# Hall_measurement.net
KiCad netlist of a schematic drawn in Altium Designer
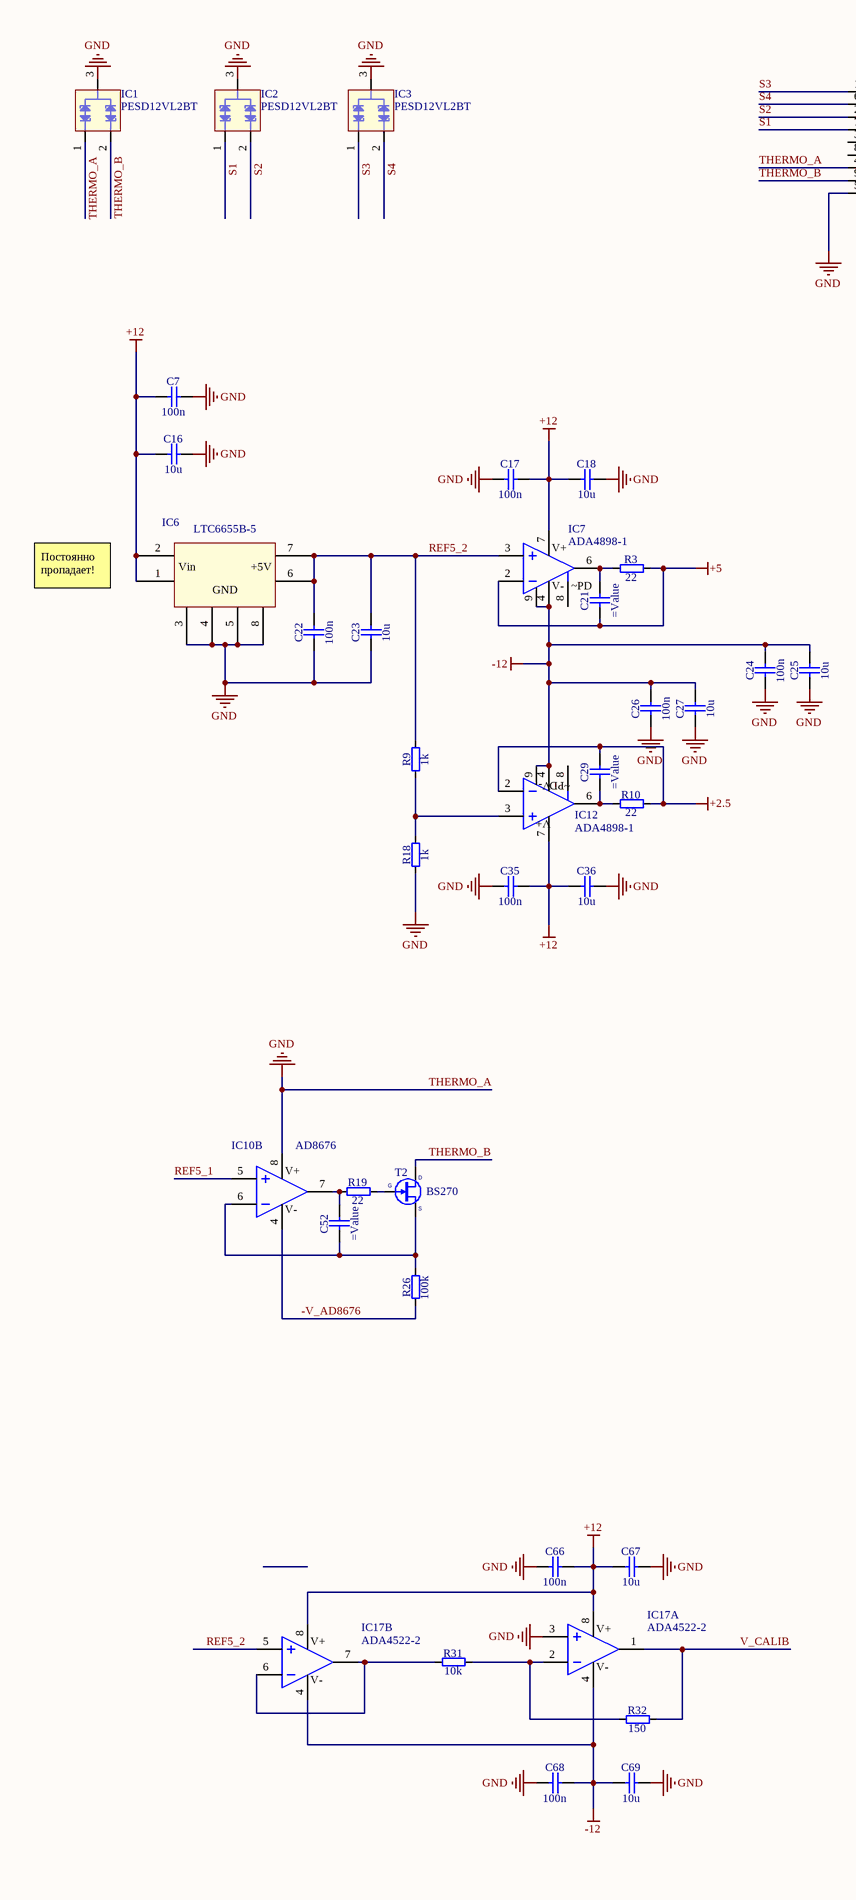
[diagram p0: Hall_measurement.SchDoc, left]
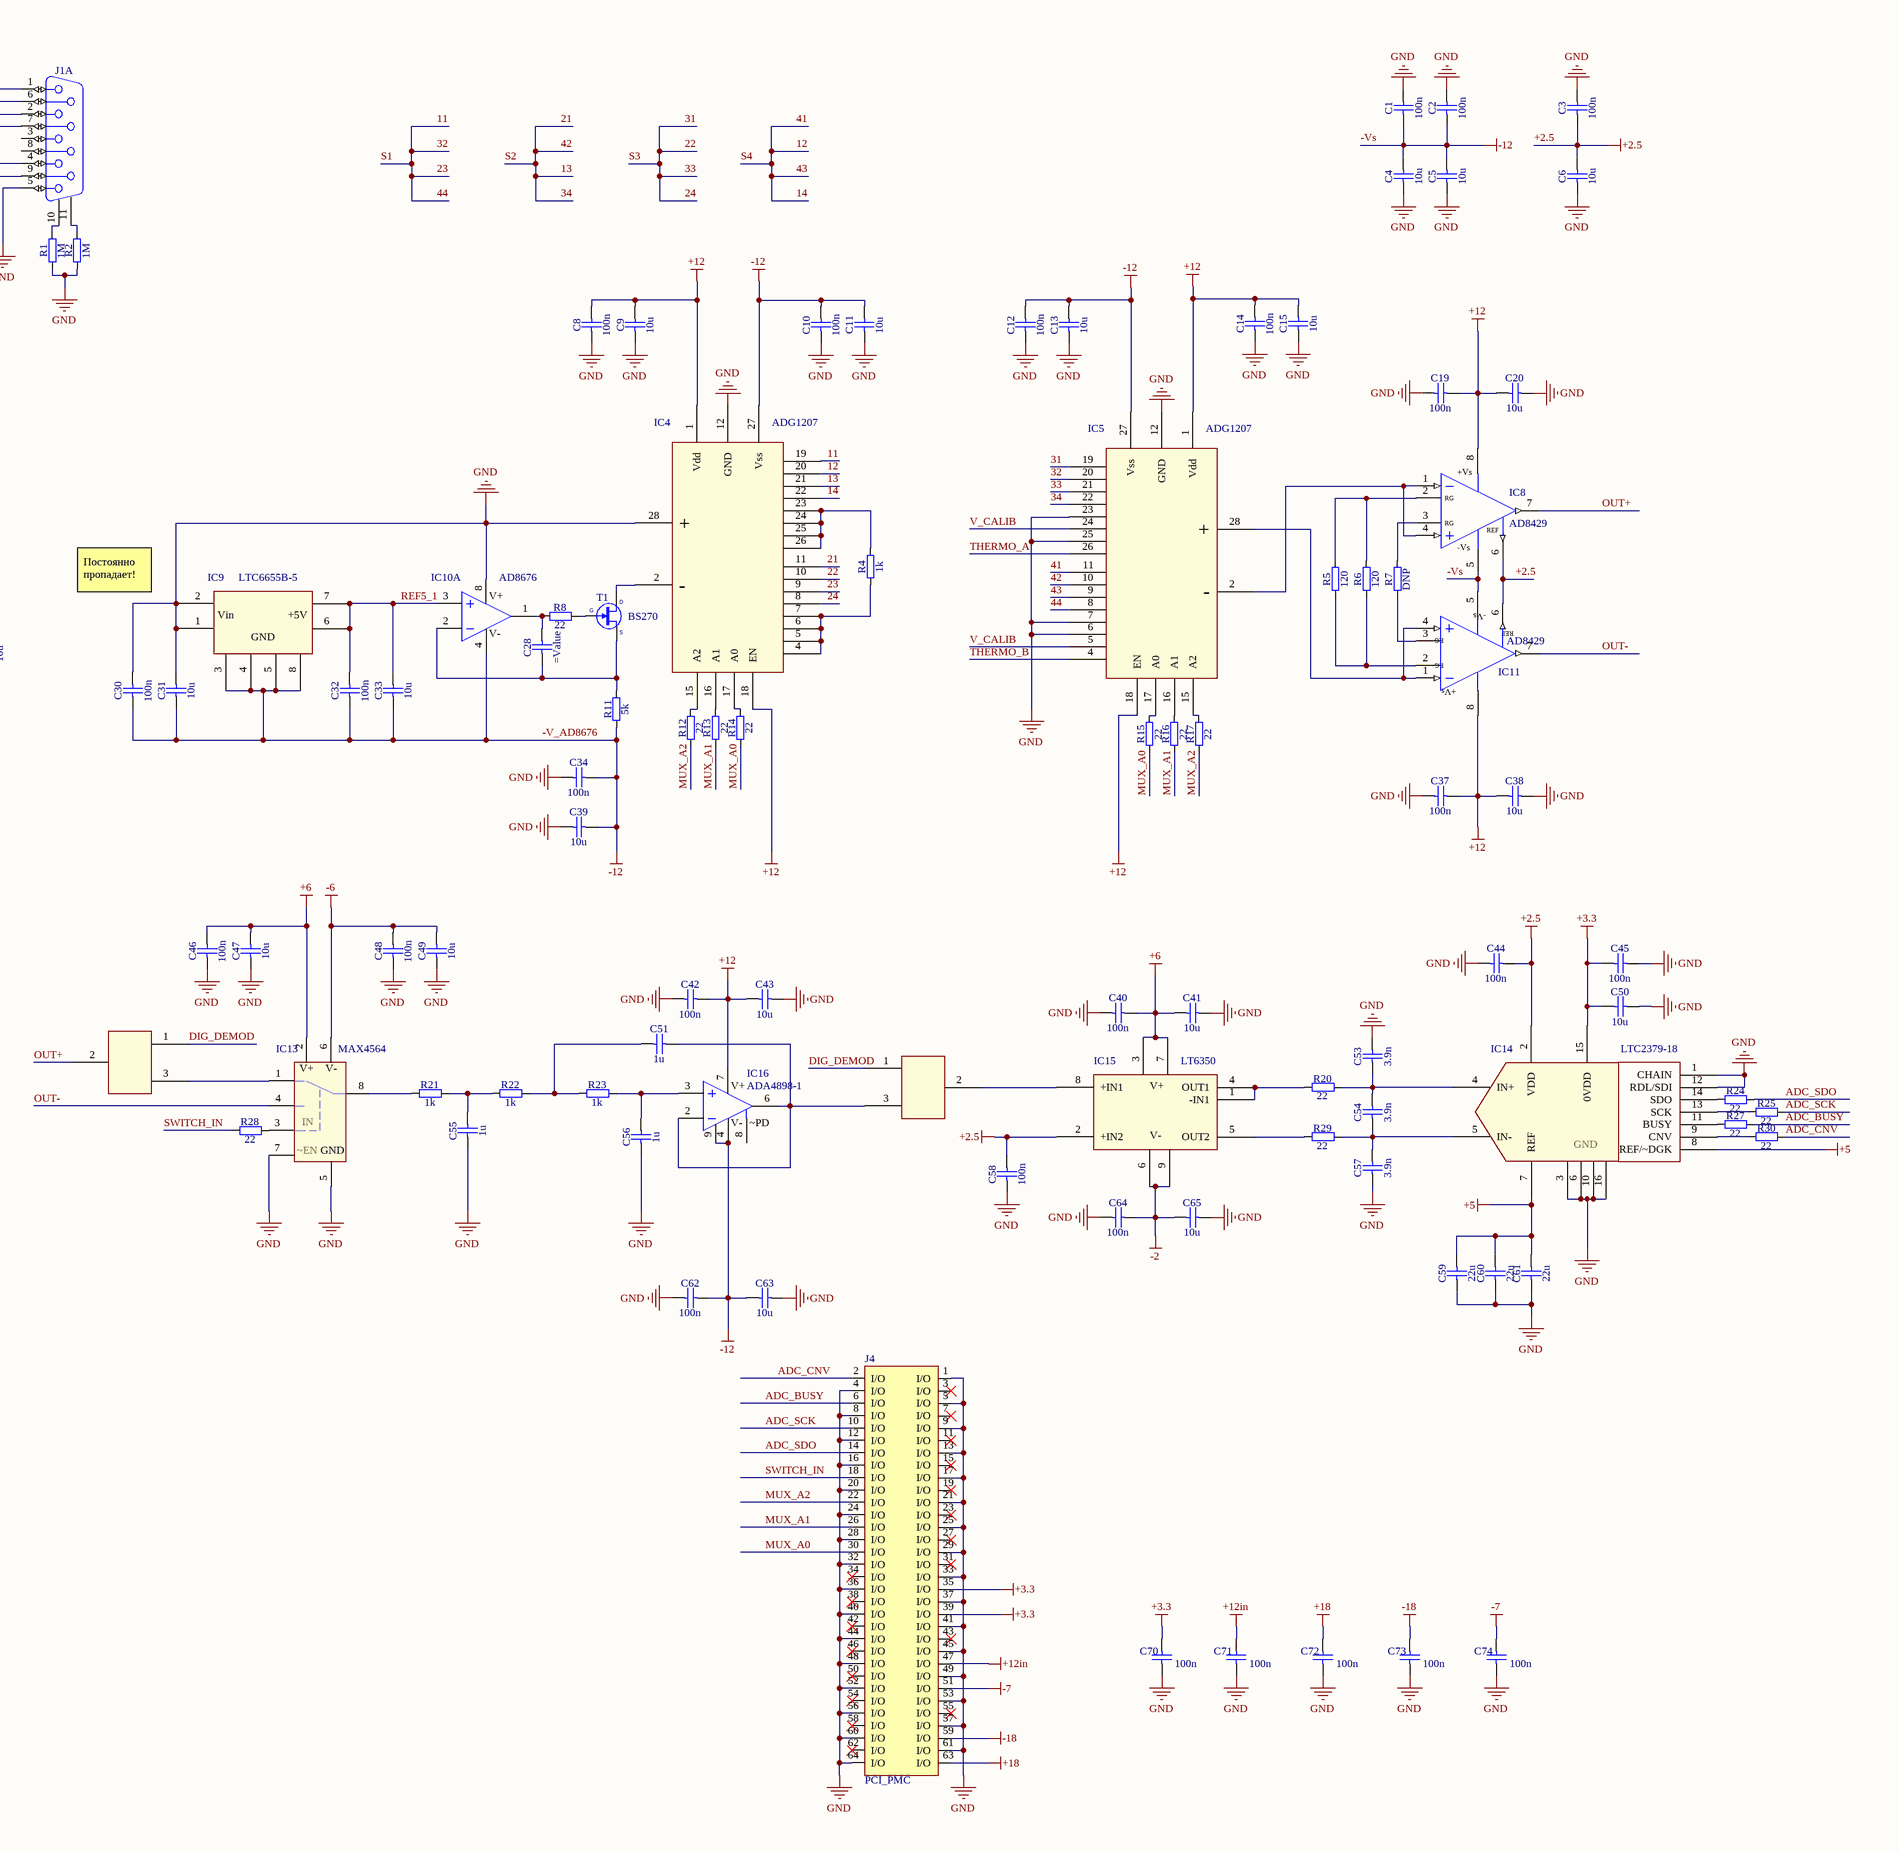
[diagram p1: Hall_measurement.SchDoc, right]

(export (version "E")
  (design (tool "Eeschema 10.0.6"))
  (components
    (comp (ref "C1") (value "100n") (footprint "0603") (libsource (lib "Lib2408_Hall") (part "Capacitor")))
    (comp (ref "C2") (value "100n") (footprint "0603") (libsource (lib "Lib2408_Hall") (part "Capacitor")))
    (comp (ref "C3") (value "100n") (footprint "0603") (libsource (lib "Lib2408_Hall") (part "Capacitor")))
    (comp (ref "C4") (value "10u") (footprint "0603") (libsource (lib "Lib2408_Hall") (part "Capacitor")))
    (comp (ref "C5") (value "10u") (footprint "0603") (libsource (lib "Lib2408_Hall") (part "Capacitor")))
    (comp (ref "C6") (value "10u") (footprint "0603") (libsource (lib "Lib2408_Hall") (part "Capacitor")))
    (comp (ref "C7") (value "100n") (footprint "0603") (libsource (lib "Lib2408_Hall") (part "Capacitor")))
    (comp (ref "C8") (value "100n") (footprint "0603") (libsource (lib "Lib2408_Hall") (part "Capacitor")))
    (comp (ref "C9") (value "10u") (footprint "0603") (libsource (lib "Lib2408_Hall") (part "Capacitor")))
    (comp (ref "C10") (value "100n") (footprint "0603") (libsource (lib "Lib2408_Hall") (part "Capacitor")))
    (comp (ref "C11") (value "10u") (footprint "0603") (libsource (lib "Lib2408_Hall") (part "Capacitor")))
    (comp (ref "C12") (value "100n") (footprint "0603") (libsource (lib "Lib2408_Hall") (part "Capacitor")))
    (comp (ref "C13") (value "10u") (footprint "0603") (libsource (lib "Lib2408_Hall") (part "Capacitor")))
    (comp (ref "C14") (value "100n") (footprint "0603") (libsource (lib "Lib2408_Hall") (part "Capacitor")))
    (comp (ref "C15") (value "10u") (footprint "0603") (libsource (lib "Lib2408_Hall") (part "Capacitor")))
    (comp (ref "C16") (value "10u") (footprint "0603") (libsource (lib "Lib2408_Hall") (part "Capacitor")))
    (comp (ref "C17") (value "100n") (footprint "0603") (libsource (lib "Lib2408_Hall") (part "Capacitor")))
    (comp (ref "C18") (value "10u") (footprint "0603") (libsource (lib "Lib2408_Hall") (part "Capacitor")))
    (comp (ref "C19") (value "100n") (footprint "0603") (libsource (lib "Lib2408_Hall") (part "Capacitor")))
    (comp (ref "C20") (value "10u") (footprint "0603") (libsource (lib "Lib2408_Hall") (part "Capacitor")))
    (comp (ref "C21") (value "~") (footprint "0603") (libsource (lib "Lib2408_Hall") (part "Capacitor")))
    (comp (ref "C22") (value "100n") (footprint "0603") (libsource (lib "Lib2408_Hall") (part "Capacitor")))
    (comp (ref "C23") (value "10u") (footprint "0603") (libsource (lib "Lib2408_Hall") (part "Capacitor")))
    (comp (ref "C24") (value "100n") (footprint "0603") (libsource (lib "Lib2408_Hall") (part "Capacitor")))
    (comp (ref "C25") (value "10u") (footprint "0603") (libsource (lib "Lib2408_Hall") (part "Capacitor")))
    (comp (ref "C26") (value "100n") (footprint "0603") (libsource (lib "Lib2408_Hall") (part "Capacitor")))
    (comp (ref "C27") (value "10u") (footprint "0603") (libsource (lib "Lib2408_Hall") (part "Capacitor")))
    (comp (ref "C28") (value "~") (footprint "0603") (libsource (lib "Lib2408_Hall") (part "Capacitor")))
    (comp (ref "C29") (value "~") (footprint "0603") (libsource (lib "Lib2408_Hall") (part "Capacitor")))
    (comp (ref "C30") (value "100n") (footprint "0603") (libsource (lib "Lib2408_Hall") (part "Capacitor")))
    (comp (ref "C31") (value "10u") (footprint "0603") (libsource (lib "Lib2408_Hall") (part "Capacitor")))
    (comp (ref "C32") (value "100n") (footprint "0603") (libsource (lib "Lib2408_Hall") (part "Capacitor")))
    (comp (ref "C33") (value "10u") (footprint "0603") (libsource (lib "Lib2408_Hall") (part "Capacitor")))
    (comp (ref "C34") (value "100n") (footprint "0603") (libsource (lib "Lib2408_Hall") (part "Capacitor")))
    (comp (ref "C35") (value "100n") (footprint "0603") (libsource (lib "Lib2408_Hall") (part "Capacitor")))
    (comp (ref "C36") (value "10u") (footprint "0603") (libsource (lib "Lib2408_Hall") (part "Capacitor")))
    (comp (ref "C37") (value "100n") (footprint "0603") (libsource (lib "Lib2408_Hall") (part "Capacitor")))
    (comp (ref "C38") (value "10u") (footprint "0603") (libsource (lib "Lib2408_Hall") (part "Capacitor")))
    (comp (ref "C39") (value "10u") (footprint "0603") (libsource (lib "Lib2408_Hall") (part "Capacitor")))
    (comp (ref "C40") (value "100n") (footprint "0603") (libsource (lib "Lib2408_Hall") (part "Capacitor")))
    (comp (ref "C41") (value "10u") (footprint "0603") (libsource (lib "Lib2408_Hall") (part "Capacitor")))
    (comp (ref "C42") (value "100n") (footprint "0603") (libsource (lib "Lib2408_Hall") (part "Capacitor")))
    (comp (ref "C43") (value "10u") (footprint "0603") (libsource (lib "Lib2408_Hall") (part "Capacitor")))
    (comp (ref "C44") (value "100n") (footprint "0603") (libsource (lib "Lib2408_Hall") (part "Capacitor")))
    (comp (ref "C45") (value "100n") (footprint "0603") (libsource (lib "Lib2408_Hall") (part "Capacitor")))
    (comp (ref "C46") (value "100n") (footprint "0603") (libsource (lib "Lib2408_Hall") (part "Capacitor")))
    (comp (ref "C47") (value "10u") (footprint "0603") (libsource (lib "Lib2408_Hall") (part "Capacitor")))
    (comp (ref "C48") (value "100n") (footprint "0603") (libsource (lib "Lib2408_Hall") (part "Capacitor")))
    (comp (ref "C49") (value "10u") (footprint "0603") (libsource (lib "Lib2408_Hall") (part "Capacitor")))
    (comp (ref "C50") (value "10u") (footprint "0603") (libsource (lib "Lib2408_Hall") (part "Capacitor")))
    (comp (ref "C51")
      (value "1u")
      (footprint "CAPR500-450X730X950")
      (libsource (lib "Lib2408_Hall") (part "Capacitor 4.5mm x 7.3mm"))
    )
    (comp (ref "C52") (value "~") (footprint "0603") (libsource (lib "Lib2408_Hall") (part "Capacitor")))
    (comp (ref "C53") (value "3.9n") (footprint "0805") (libsource (lib "Lib2408_Hall") (part "Capacitor")))
    (comp (ref "C54") (value "3.9n") (footprint "0805") (libsource (lib "Lib2408_Hall") (part "Capacitor")))
    (comp (ref "C55")
      (value "1u")
      (footprint "CAPR500-450X730X950")
      (libsource (lib "Lib2408_Hall") (part "Capacitor 4.5mm x 7.3mm"))
    )
    (comp (ref "C56")
      (value "1u")
      (footprint "CAPR500-450X730X950")
      (libsource (lib "Lib2408_Hall") (part "Capacitor 4.5mm x 7.3mm"))
    )
    (comp (ref "C57") (value "3.9n") (footprint "0805") (libsource (lib "Lib2408_Hall") (part "Capacitor")))
    (comp (ref "C58") (value "100n") (footprint "0603") (libsource (lib "Lib2408_Hall") (part "Capacitor")))
    (comp (ref "C59") (value "22u") (footprint "0603") (libsource (lib "Lib2408_Hall") (part "Capacitor")))
    (comp (ref "C60") (value "22u") (footprint "0603") (libsource (lib "Lib2408_Hall") (part "Capacitor")))
    (comp (ref "C61") (value "22u") (footprint "0603") (libsource (lib "Lib2408_Hall") (part "Capacitor")))
    (comp (ref "C62") (value "100n") (footprint "0603") (libsource (lib "Lib2408_Hall") (part "Capacitor")))
    (comp (ref "C63") (value "10u") (footprint "0603") (libsource (lib "Lib2408_Hall") (part "Capacitor")))
    (comp (ref "C64") (value "100n") (footprint "0603") (libsource (lib "Lib2408_Hall") (part "Capacitor")))
    (comp (ref "C65") (value "10u") (footprint "0603") (libsource (lib "Lib2408_Hall") (part "Capacitor")))
    (comp (ref "C66") (value "100n") (footprint "0603") (libsource (lib "Lib2408_Hall") (part "Capacitor")))
    (comp (ref "C67") (value "10u") (footprint "0603") (libsource (lib "Lib2408_Hall") (part "Capacitor")))
    (comp (ref "C68") (value "100n") (footprint "0603") (libsource (lib "Lib2408_Hall") (part "Capacitor")))
    (comp (ref "C69") (value "10u") (footprint "0603") (libsource (lib "Lib2408_Hall") (part "Capacitor")))
    (comp (ref "C70") (value "100n") (footprint "0603") (libsource (lib "Lib2408_Hall") (part "Capacitor")))
    (comp (ref "C71") (value "100n") (footprint "0603") (libsource (lib "Lib2408_Hall") (part "Capacitor")))
    (comp (ref "C72") (value "100n") (footprint "0603") (libsource (lib "Lib2408_Hall") (part "Capacitor")))
    (comp (ref "C73") (value "100n") (footprint "0603") (libsource (lib "Lib2408_Hall") (part "Capacitor")))
    (comp (ref "C74") (value "100n") (footprint "0603") (libsource (lib "Lib2408_Hall") (part "Capacitor")))
    (comp (ref "IC1")
      (value "PESD12VL2BT")
      (footprint "SOT95P280X115-3N")
      (libsource (lib "Lib2408_Hall") (part "PESD12VL2BT"))
    )
    (comp (ref "IC2")
      (value "PESD12VL2BT")
      (footprint "SOT95P280X115-3N")
      (libsource (lib "Lib2408_Hall") (part "PESD12VL2BT"))
    )
    (comp (ref "IC3")
      (value "PESD12VL2BT")
      (footprint "SOT95P280X115-3N")
      (libsource (lib "Lib2408_Hall") (part "PESD12VL2BT"))
    )
    (comp (ref "IC4")
      (value "ADG1207")
      (footprint "SOP65P640X120-28N")
      (description "8-channel multiplexer")
      (libsource (lib "") (part "ADG1207_1"))
    )
    (comp (ref "IC5")
      (value "ADG1207")
      (footprint "SOP65P640X120-28N")
      (description "8-channel multiplexer")
      (libsource (lib "Lib2408_Hall") (part "ADG1207"))
    )
    (comp (ref "IC6")
      (value "LTC6655B-5")
      (footprint "SOP65P488X110-8N")
      (description "Reference, 5 V")
      (libsource (lib "Lib2408_Hall") (part "LTC6655B-5"))
    )
    (comp (ref "IC7")
      (value "ADA4898-1")
      (footprint "SOIC127P600X175-9N-S229")
      (description "Op amp")
      (libsource (lib "Lib2408_Hall") (part "ADA4898-1"))
    )
    (comp (ref "IC8")
      (value "AD8429")
      (footprint "SOIC127P600X175-8N")
      (description "1 nV/sqrt Hz Low Noise Instrumentation Amplifier")
      (libsource (lib "Lib2408_Hall") (part "AD8429"))
    )
    (comp (ref "IC9")
      (value "LTC6655B-5")
      (footprint "SOP65P488X110-8N")
      (description "Reference, 5 V")
      (libsource (lib "Lib2408_Hall") (part "LTC6655B-5"))
    )
    (comp (ref "IC10")
      (value "AD8676")
      (footprint "SOIC127P600X175-8N")
      (description "Dual Op Amp")
      (libsource (lib "Lib2408_Hall") (part "AD8676"))
    )
    (comp (ref "IC11")
      (value "AD8429")
      (footprint "SOIC127P600X175-8N")
      (description "1 nV/sqrt Hz Low Noise Instrumentation Amplifier")
      (libsource (lib "Lib2408_Hall") (part "AD8429"))
    )
    (comp (ref "IC12")
      (value "ADA4898-1")
      (footprint "SOIC127P600X175-9N-S229")
      (description "Op amp")
      (libsource (lib "Lib2408_Hall") (part "ADA4898-1"))
    )
    (comp (ref "IC13")
      (value "MAX4564")
      (footprint "SOT65P280X100-8N")
      (description "Switch")
      (libsource (lib "Lib2408_Hall") (part "MAX4564"))
    )
    (comp (ref "IC14")
      (value "LTC2379-18")
      (footprint "SOP50P490X110-16N")
      (description "ADC")
      (libsource (lib "Lib2408_Hall") (part "LTC2379-18"))
    )
    (comp (ref "IC15")
      (value "LT6350")
      (footprint "SON50P300X300X80-9N-R175X248")
      (description "ADC driver")
      (libsource (lib "Lib2408_Hall") (part "LT6350"))
    )
    (comp (ref "IC16")
      (value "ADA4898-1")
      (footprint "SOIC127P600X175-9N-S229")
      (description "Op amp")
      (libsource (lib "Lib2408_Hall") (part "ADA4898-1"))
    )
    (comp (ref "IC17")
      (value "ADA4522-2")
      (footprint "SOIC127P600X175-8N")
      (description "Dual Op Amp")
      (libsource (lib "Lib2408_Hall") (part "ADA4522-2"))
    )
    (comp (ref "J1")
      (value "~")
      (footprint "TYCO_5747844-5")
      (description "Connector D-sub 2x9 Female")
      (libsource (lib "Lib2408_Hall") (part "Connector D-sub 2x9 Female"))
    )
    (comp (ref "J2") (value "Jumper") (footprint "Jumper") (libsource (lib "") (part "Jumper_1")))
    (comp (ref "J3") (value "Jumper") (footprint "Jumper") (libsource (lib "Lib2408_Hall") (part "Jumper")))
    (comp (ref "J4")
      (value "PCI_PMC")
      (footprint "TYCO_120527-1")
      (description "PCI Mezzanine Connector; IEEE 1386 Mezzanine board")
      (libsource (lib "Lib2408") (part "PCI_PMC"))
    )
    (comp (ref "R1") (value "1M") (footprint "0603") (libsource (lib "Lib2408_Hall") (part "Resistor")))
    (comp (ref "R2") (value "1M") (footprint "0603") (libsource (lib "Lib2408_Hall") (part "Resistor")))
    (comp (ref "R3") (value "22") (footprint "0603") (libsource (lib "Lib2408_Hall") (part "Resistor")))
    (comp (ref "R4") (value "1k") (footprint "0603") (libsource (lib "Lib2408_Hall") (part "Resistor")))
    (comp (ref "R5") (value "120") (footprint "0805") (libsource (lib "Lib2408_Hall") (part "Resistor")))
    (comp (ref "R6") (value "120") (footprint "0805") (libsource (lib "Lib2408_Hall") (part "Resistor")))
    (comp (ref "R7") (value "DNP") (footprint "0805") (libsource (lib "Lib2408_Hall") (part "Resistor")))
    (comp (ref "R8") (value "22") (footprint "0603") (libsource (lib "Lib2408_Hall") (part "Resistor")))
    (comp (ref "R9") (value "1k") (footprint "0805") (libsource (lib "Lib2408_Hall") (part "Resistor")))
    (comp (ref "R10") (value "22") (footprint "0603") (libsource (lib "Lib2408_Hall") (part "Resistor")))
    (comp (ref "R11") (value "5k") (footprint "1206") (libsource (lib "Lib2408_Hall") (part "Resistor")))
    (comp (ref "R12") (value "22") (footprint "0603") (libsource (lib "Lib2408_Hall") (part "Resistor")))
    (comp (ref "R13") (value "22") (footprint "0603") (libsource (lib "Lib2408_Hall") (part "Resistor")))
    (comp (ref "R14") (value "22") (footprint "0603") (libsource (lib "Lib2408_Hall") (part "Resistor")))
    (comp (ref "R15") (value "22") (footprint "0603") (libsource (lib "Lib2408_Hall") (part "Resistor")))
    (comp (ref "R16") (value "22") (footprint "0603") (libsource (lib "Lib2408_Hall") (part "Resistor")))
    (comp (ref "R17") (value "22") (footprint "0603") (libsource (lib "Lib2408_Hall") (part "Resistor")))
    (comp (ref "R18") (value "1k") (footprint "0805") (libsource (lib "Lib2408_Hall") (part "Resistor")))
    (comp (ref "R19") (value "22") (footprint "0603") (libsource (lib "Lib2408_Hall") (part "Resistor")))
    (comp (ref "R20") (value "22") (footprint "0805") (libsource (lib "Lib2408_Hall") (part "Resistor")))
    (comp (ref "R21") (value "1k") (footprint "0805") (libsource (lib "Lib2408_Hall") (part "Resistor")))
    (comp (ref "R22") (value "1k") (footprint "0805") (libsource (lib "Lib2408_Hall") (part "Resistor")))
    (comp (ref "R23") (value "1k") (footprint "0805") (libsource (lib "Lib2408_Hall") (part "Resistor")))
    (comp (ref "R24") (value "22") (footprint "0603") (libsource (lib "Lib2408_Hall") (part "Resistor")))
    (comp (ref "R25") (value "22") (footprint "0603") (libsource (lib "Lib2408_Hall") (part "Resistor")))
    (comp (ref "R26") (value "100k") (footprint "1206") (libsource (lib "Lib2408_Hall") (part "Resistor")))
    (comp (ref "R27") (value "22") (footprint "0603") (libsource (lib "Lib2408_Hall") (part "Resistor")))
    (comp (ref "R28") (value "22") (footprint "0603") (libsource (lib "Lib2408_Hall") (part "Resistor")))
    (comp (ref "R29") (value "22") (footprint "0805") (libsource (lib "Lib2408_Hall") (part "Resistor")))
    (comp (ref "R30") (value "22") (footprint "0603") (libsource (lib "Lib2408_Hall") (part "Resistor")))
    (comp (ref "R31") (value "10k") (footprint "0805") (libsource (lib "Lib2408_Hall") (part "Resistor")))
    (comp (ref "R32") (value "150") (footprint "0805") (libsource (lib "Lib2408_Hall") (part "Resistor")))
    (comp (ref "T1")
      (value "BS270")
      (footprint "TO-92AA-P127")
      (libsource (lib "Lib2408_Hall") (part "Transistor"))
    )
    (comp (ref "T2")
      (value "BS270")
      (footprint "TO-92AA-P127")
      (libsource (lib "Lib2408_Hall") (part "Transistor"))
    )
  )
  (nets
    (net (code "1") (name "+2.5") (class "Default")
      (node (ref "C29") (pin "2") (pinfunction "2_2") (pintype "passive"))
      (node (ref "C3") (pin "1") (pinfunction "1_1") (pintype "passive"))
      (node (ref "C44") (pin "2") (pinfunction "2_2") (pintype "passive"))
      (node (ref "C58") (pin "2") (pinfunction "2_2") (pintype "passive"))
      (node (ref "C6") (pin "2") (pinfunction "2_2") (pintype "passive"))
      (node (ref "IC11") (pin "6") (pinfunction "REF_6") (pintype "output"))
      (node (ref "IC12") (pin "2") (pinfunction "IN-_2") (pintype "passive"))
      (node (ref "IC14") (pin "2") (pinfunction "VDD_2") (pintype "passive"))
      (node (ref "IC15") (pin "2") (pinfunction "+IN2_2") (pintype "passive"))
      (node (ref "IC8") (pin "6") (pinfunction "REF_6") (pintype "output"))
      (node (ref "R10") (pin "2") (pinfunction "2_2") (pintype "passive"))
    )
    (net (code "2") (name "+3.3") (class "Default")
      (node (ref "C45") (pin "1") (pinfunction "1_1") (pintype "passive"))
      (node (ref "C50") (pin "1") (pinfunction "1_1") (pintype "passive"))
      (node (ref "C70") (pin "2") (pinfunction "2_2") (pintype "passive"))
      (node (ref "IC14") (pin "15") (pinfunction "0VDD_15") (pintype "passive"))
      (node (ref "J4") (pin "35") (pinfunction "I/O_35") (pintype "bidirectional"))
      (node (ref "J4") (pin "39") (pinfunction "I/O_39") (pintype "bidirectional"))
    )
    (net (code "3") (name "+5") (class "Default")
      (node (ref "C21") (pin "1") (pinfunction "1_1") (pintype "passive"))
      (node (ref "C59") (pin "2") (pinfunction "2_2") (pintype "passive"))
      (node (ref "C60") (pin "2") (pinfunction "2_2") (pintype "passive"))
      (node (ref "C61") (pin "2") (pinfunction "2_2") (pintype "passive"))
      (node (ref "IC14") (pin "7") (pinfunction "REF_7") (pintype "passive"))
      (node (ref "IC14") (pin "8") (pinfunction "REF/~DGK_8") (pintype "passive"))
      (node (ref "IC7") (pin "2") (pinfunction "IN-_2") (pintype "passive"))
      (node (ref "R3") (pin "2") (pinfunction "2_2") (pintype "passive"))
    )
    (net (code "4") (name "+6") (class "Default")
      (node (ref "C40") (pin "2") (pinfunction "2_2") (pintype "passive"))
      (node (ref "C41") (pin "1") (pinfunction "1_1") (pintype "passive"))
      (node (ref "C46") (pin "2") (pinfunction "2_2") (pintype "passive"))
      (node (ref "C47") (pin "2") (pinfunction "2_2") (pintype "passive"))
      (node (ref "IC13") (pin "2") (pinfunction "V+_2") (pintype "passive"))
      (node (ref "IC15") (pin "3") (pinfunction "V+_3") (pintype "passive"))
      (node (ref "IC15") (pin "7") (pintype "passive"))
    )
    (net (code "5") (name "+12") (class "Default")
      (node (ref "C14") (pin "2") (pinfunction "2_2") (pintype "passive"))
      (node (ref "C15") (pin "2") (pinfunction "2_2") (pintype "passive"))
      (node (ref "C16") (pin "1") (pinfunction "1_1") (pintype "passive"))
      (node (ref "C17") (pin "2") (pinfunction "2_2") (pintype "passive"))
      (node (ref "C18") (pin "1") (pinfunction "1_1") (pintype "passive"))
      (node (ref "C19") (pin "2") (pinfunction "2_2") (pintype "passive"))
      (node (ref "C20") (pin "1") (pinfunction "1_1") (pintype "passive"))
      (node (ref "C35") (pin "1") (pinfunction "1_1") (pintype "passive"))
      (node (ref "C36") (pin "2") (pinfunction "2_2") (pintype "passive"))
      (node (ref "C37") (pin "2") (pinfunction "2_2") (pintype "passive"))
      (node (ref "C38") (pin "1") (pinfunction "1_1") (pintype "passive"))
      (node (ref "C42") (pin "2") (pinfunction "2_2") (pintype "passive"))
      (node (ref "C43") (pin "1") (pinfunction "1_1") (pintype "passive"))
      (node (ref "C66") (pin "2") (pinfunction "2_2") (pintype "passive"))
      (node (ref "C67") (pin "1") (pinfunction "1_1") (pintype "passive"))
      (node (ref "C7") (pin "1") (pinfunction "1_1") (pintype "passive"))
      (node (ref "C8") (pin "2") (pinfunction "2_2") (pintype "passive"))
      (node (ref "C9") (pin "2") (pinfunction "2_2") (pintype "passive"))
      (node (ref "IC11") (pin "8") (pinfunction "+Vs_8") (pintype "power_in"))
      (node (ref "IC12") (pin "7") (pinfunction "V+_7") (pintype "passive"))
      (node (ref "IC16") (pin "7") (pinfunction "V+_7") (pintype "passive"))
      (node (ref "IC17") (pin "8") (pinfunction "V+_8") (pintype "passive"))
      (node (ref "IC4") (pin "1") (pinfunction "Vdd_1") (pintype "passive"))
      (node (ref "IC4") (pin "18") (pinfunction "EN_18") (pintype "passive"))
      (node (ref "IC5") (pin "1") (pinfunction "Vdd_1") (pintype "passive"))
      (node (ref "IC5") (pin "18") (pinfunction "EN_18") (pintype "passive"))
      (node (ref "IC6") (pin "1") (pintype "passive"))
      (node (ref "IC6") (pin "2") (pintype "passive"))
      (node (ref "IC7") (pin "7") (pinfunction "V+_7") (pintype "passive"))
      (node (ref "IC8") (pin "8") (pinfunction "+Vs_8") (pintype "power_in"))
    )
    (net (code "6") (name "+12in") (class "Default")
      (node (ref "C71") (pin "2") (pinfunction "2_2") (pintype "passive"))
      (node (ref "J4") (pin "47") (pinfunction "I/O_47") (pintype "bidirectional"))
    )
    (net (code "7") (name "+18") (class "Default")
      (node (ref "C72") (pin "2") (pinfunction "2_2") (pintype "passive"))
      (node (ref "J4") (pin "63") (pinfunction "I/O_63") (pintype "bidirectional"))
    )
    (net (code "8") (name "-2") (class "Default")
      (node (ref "C64") (pin "2") (pinfunction "2_2") (pintype "passive"))
      (node (ref "C65") (pin "1") (pinfunction "1_1") (pintype "passive"))
      (node (ref "IC15") (pin "6") (pinfunction "V-_6") (pintype "passive"))
      (node (ref "IC15") (pin "9") (pinfunction "V-_9") (pintype "passive"))
    )
    (net (code "9") (name "-6") (class "Default")
      (node (ref "C48") (pin "2") (pinfunction "2_2") (pintype "passive"))
      (node (ref "C49") (pin "2") (pinfunction "2_2") (pintype "passive"))
      (node (ref "IC13") (pin "6") (pinfunction "V-_6") (pintype "passive"))
    )
    (net (code "10") (name "-7") (class "Default")
      (node (ref "C74") (pin "2") (pinfunction "2_2") (pintype "passive"))
      (node (ref "J4") (pin "51") (pinfunction "I/O_51") (pintype "bidirectional"))
    )
    (net (code "11") (name "-12") (class "Default")
      (node (ref "C1") (pin "1") (pinfunction "1_1") (pintype "passive"))
      (node (ref "C10") (pin "2") (pinfunction "2_2") (pintype "passive"))
      (node (ref "C11") (pin "2") (pinfunction "2_2") (pintype "passive"))
      (node (ref "C12") (pin "2") (pinfunction "2_2") (pintype "passive"))
      (node (ref "C13") (pin "2") (pinfunction "2_2") (pintype "passive"))
      (node (ref "C2") (pin "1") (pinfunction "1_1") (pintype "passive"))
      (node (ref "C24") (pin "2") (pinfunction "2_2") (pintype "passive"))
      (node (ref "C25") (pin "2") (pinfunction "2_2") (pintype "passive"))
      (node (ref "C26") (pin "2") (pinfunction "2_2") (pintype "passive"))
      (node (ref "C27") (pin "2") (pinfunction "2_2") (pintype "passive"))
      (node (ref "C30") (pin "1") (pinfunction "1_1") (pintype "passive"))
      (node (ref "C31") (pin "1") (pinfunction "1_1") (pintype "passive"))
      (node (ref "C32") (pin "1") (pinfunction "1_1") (pintype "passive"))
      (node (ref "C33") (pin "1") (pinfunction "1_1") (pintype "passive"))
      (node (ref "C34") (pin "2") (pinfunction "2_2") (pintype "passive"))
      (node (ref "C39") (pin "1") (pinfunction "1_1") (pintype "passive"))
      (node (ref "C4") (pin "2") (pinfunction "2_2") (pintype "passive"))
      (node (ref "C5") (pin "2") (pinfunction "2_2") (pintype "passive"))
      (node (ref "C62") (pin "2") (pinfunction "2_2") (pintype "passive"))
      (node (ref "C63") (pin "1") (pinfunction "1_1") (pintype "passive"))
      (node (ref "C68") (pin "2") (pinfunction "2_2") (pintype "passive"))
      (node (ref "C69") (pin "1") (pinfunction "1_1") (pintype "passive"))
      (node (ref "IC10") (pin "4") (pinfunction "V-_4") (pintype "passive"))
      (node (ref "IC11") (pin "5") (pinfunction "-Vs_5") (pintype "power_in"))
      (node (ref "IC12") (pin "4") (pinfunction "V-_4") (pintype "passive"))
      (node (ref "IC12") (pin "9") (pinfunction "EXPOSED_PAD_9") (pintype "passive"))
      (node (ref "IC16") (pin "4") (pinfunction "V-_4") (pintype "passive"))
      (node (ref "IC16") (pin "9") (pinfunction "EXPOSED_PAD_9") (pintype "passive"))
      (node (ref "IC17") (pin "4") (pinfunction "V-_4") (pintype "passive"))
      (node (ref "IC4") (pin "27") (pinfunction "Vss_27") (pintype "passive"))
      (node (ref "IC5") (pin "27") (pinfunction "Vss_27") (pintype "passive"))
      (node (ref "IC7") (pin "4") (pinfunction "V-_4") (pintype "passive"))
      (node (ref "IC7") (pin "9") (pinfunction "EXPOSED_PAD_9") (pintype "passive"))
      (node (ref "IC8") (pin "5") (pinfunction "-Vs_5") (pintype "power_in"))
      (node (ref "IC9") (pin "3") (pintype "passive"))
      (node (ref "IC9") (pin "4") (pintype "passive"))
      (node (ref "IC9") (pin "5") (pintype "passive"))
      (node (ref "IC9") (pin "8") (pintype "passive"))
      (node (ref "R11") (pin "1") (pinfunction "1_1") (pintype "passive"))
      (node (ref "R26") (pin "1") (pinfunction "1_1") (pintype "passive"))
    )
    (net (code "12") (name "-18") (class "Default")
      (node (ref "C73") (pin "2") (pinfunction "2_2") (pintype "passive"))
      (node (ref "J4") (pin "59") (pinfunction "I/O_59") (pintype "bidirectional"))
    )
    (net (code "13") (name "/11") (class "Default")
      (node (ref "IC2") (pin "1") (pinfunction "C1_1") (pintype "passive"))
      (node (ref "IC4") (pin "19") (pintype "passive"))
      (node (ref "IC4") (pin "9") (pintype "passive"))
      (node (ref "IC5") (pin "20") (pintype "passive"))
      (node (ref "IC5") (pin "8") (pintype "passive"))
      (node (ref "J1") (pin "7") (pinfunction "U7_7") (pintype "bidirectional"))
    )
    (net (code "14") (name "/12") (class "Default")
      (node (ref "IC3") (pin "2") (pinfunction "C2_2") (pintype "passive"))
      (node (ref "IC4") (pin "20") (pintype "passive"))
      (node (ref "IC4") (pin "22") (pintype "passive"))
      (node (ref "IC5") (pin "11") (pintype "passive"))
      (node (ref "IC5") (pin "9") (pintype "passive"))
      (node (ref "J1") (pin "6") (pinfunction "U6_6") (pintype "bidirectional"))
    )
    (net (code "15") (name "/13") (class "Default")
      (node (ref "IC2") (pin "2") (pinfunction "C2_2") (pintype "passive"))
      (node (ref "IC4") (pin "11") (pintype "passive"))
      (node (ref "IC4") (pin "21") (pintype "passive"))
      (node (ref "IC5") (pin "10") (pintype "passive"))
      (node (ref "IC5") (pin "22") (pintype "passive"))
      (node (ref "J1") (pin "2") (pinfunction "U2_2") (pintype "bidirectional"))
    )
    (net (code "16") (name "/22") (class "Default")
      (node (ref "IC3") (pin "1") (pinfunction "C1_1") (pintype "passive"))
      (node (ref "IC4") (pin "10") (pintype "passive"))
      (node (ref "IC4") (pin "8") (pintype "passive"))
      (node (ref "IC5") (pin "19") (pintype "passive"))
      (node (ref "IC5") (pin "21") (pintype "passive"))
      (node (ref "J1") (pin "1") (pinfunction "U1_1") (pintype "bidirectional"))
    )
    (net (code "17") (name "/ADC_BUSY") (class "Default")
      (node (ref "J4") (pin "6") (pinfunction "I/O_6") (pintype "bidirectional"))
      (node (ref "R27") (pin "2") (pinfunction "2_2") (pintype "passive"))
    )
    (net (code "18") (name "/ADC_CNV") (class "Default")
      (node (ref "J4") (pin "2") (pinfunction "I/O_2") (pintype "bidirectional"))
      (node (ref "R30") (pin "2") (pinfunction "2_2") (pintype "passive"))
    )
    (net (code "19") (name "/ADC_SCK") (class "Default")
      (node (ref "J4") (pin "10") (pinfunction "I/O_10") (pintype "bidirectional"))
      (node (ref "R25") (pin "2") (pinfunction "2_2") (pintype "passive"))
    )
    (net (code "20") (name "/ADC_SDO") (class "Default")
      (node (ref "J4") (pin "14") (pinfunction "I/O_14") (pintype "bidirectional"))
      (node (ref "R24") (pin "2") (pinfunction "2_2") (pintype "passive"))
    )
    (net (code "21") (name "/DIG_DEMOD") (class "Default")
      (node (ref "J2") (pin "1") (pinfunction "1_1") (pintype "passive"))
      (node (ref "J3") (pin "1") (pinfunction "1_1") (pintype "passive"))
    )
    (net (code "22") (name "/MUX_A0") (class "Default")
      (node (ref "J4") (pin "30") (pinfunction "I/O_30") (pintype "bidirectional"))
      (node (ref "R14") (pin "1") (pinfunction "1_1") (pintype "passive"))
      (node (ref "R15") (pin "1") (pinfunction "1_1") (pintype "passive"))
    )
    (net (code "23") (name "/MUX_A1") (class "Default")
      (node (ref "J4") (pin "26") (pinfunction "I/O_26") (pintype "bidirectional"))
      (node (ref "R13") (pin "1") (pinfunction "1_1") (pintype "passive"))
      (node (ref "R16") (pin "1") (pinfunction "1_1") (pintype "passive"))
    )
    (net (code "24") (name "/MUX_A2") (class "Default")
      (node (ref "J4") (pin "22") (pinfunction "I/O_22") (pintype "bidirectional"))
      (node (ref "R12") (pin "1") (pinfunction "1_1") (pintype "passive"))
      (node (ref "R17") (pin "1") (pinfunction "1_1") (pintype "passive"))
    )
    (net (code "25") (name "/OUT+") (class "Default")
      (node (ref "IC8") (pin "7") (pinfunction "Vout_7") (pintype "output"))
      (node (ref "J2") (pin "2") (pinfunction "2_2") (pintype "passive"))
    )
    (net (code "26") (name "/OUT-") (class "Default")
      (node (ref "IC11") (pin "7") (pinfunction "Vout_7") (pintype "output"))
      (node (ref "IC13") (pin "4") (pinfunction "NO_4") (pintype "passive"))
    )
    (net (code "27") (name "/REF5_1") (class "Default")
      (node (ref "C32") (pin "2") (pinfunction "2_2") (pintype "passive"))
      (node (ref "C33") (pin "2") (pinfunction "2_2") (pintype "passive"))
      (node (ref "IC10") (pin "3") (pinfunction "+IN_A_3") (pintype "passive"))
      (node (ref "IC10") (pin "5") (pinfunction "+IN_B_5") (pintype "passive"))
      (node (ref "IC9") (pin "6") (pintype "passive"))
      (node (ref "IC9") (pin "7") (pintype "passive"))
    )
    (net (code "28") (name "/REF5_2") (class "Default")
      (node (ref "C22") (pin "2") (pinfunction "2_2") (pintype "passive"))
      (node (ref "C23") (pin "2") (pinfunction "2_2") (pintype "passive"))
      (node (ref "IC17") (pin "5") (pinfunction "+IN_B_5") (pintype "passive"))
      (node (ref "IC6") (pin "6") (pintype "passive"))
      (node (ref "IC6") (pin "7") (pintype "passive"))
      (node (ref "IC7") (pin "3") (pinfunction "IN+_3") (pintype "passive"))
      (node (ref "R9") (pin "2") (pinfunction "2_2") (pintype "passive"))
    )
    (net (code "29") (name "/SWITCH_IN") (class "Default")
      (node (ref "J4") (pin "18") (pinfunction "I/O_18") (pintype "bidirectional"))
      (node (ref "R28") (pin "1") (pinfunction "1_1") (pintype "passive"))
    )
    (net (code "30") (name "/THERMO_B") (class "Default")
      (node (ref "IC1") (pin "2") (pinfunction "C2_2") (pintype "passive"))
      (node (ref "IC5") (pin "4") (pintype "passive"))
      (node (ref "J1") (pin "9") (pinfunction "U9_9") (pintype "bidirectional"))
      (node (ref "T2") (pin "1") (pinfunction "D_1") (pintype "passive"))
    )
    (net (code "31") (name "/V_CALIB") (class "Default")
      (node (ref "IC17") (pin "1") (pinfunction "OUT_A_1") (pintype "passive"))
      (node (ref "IC5") (pin "24") (pintype "passive"))
      (node (ref "IC5") (pin "5") (pintype "passive"))
      (node (ref "R32") (pin "2") (pinfunction "2_2") (pintype "passive"))
    )
    (net (code "32") (name "GND") (class "Default")
      (node (ref "C1") (pin "2") (pinfunction "2_2") (pintype "passive"))
      (node (ref "C10") (pin "1") (pinfunction "1_1") (pintype "passive"))
      (node (ref "C11") (pin "1") (pinfunction "1_1") (pintype "passive"))
      (node (ref "C12") (pin "1") (pinfunction "1_1") (pintype "passive"))
      (node (ref "C13") (pin "1") (pinfunction "1_1") (pintype "passive"))
      (node (ref "C14") (pin "1") (pinfunction "1_1") (pintype "passive"))
      (node (ref "C15") (pin "1") (pinfunction "1_1") (pintype "passive"))
      (node (ref "C16") (pin "2") (pinfunction "2_2") (pintype "passive"))
      (node (ref "C17") (pin "1") (pinfunction "1_1") (pintype "passive"))
      (node (ref "C18") (pin "2") (pinfunction "2_2") (pintype "passive"))
      (node (ref "C19") (pin "1") (pinfunction "1_1") (pintype "passive"))
      (node (ref "C2") (pin "2") (pinfunction "2_2") (pintype "passive"))
      (node (ref "C20") (pin "2") (pinfunction "2_2") (pintype "passive"))
      (node (ref "C22") (pin "1") (pinfunction "1_1") (pintype "passive"))
      (node (ref "C23") (pin "1") (pinfunction "1_1") (pintype "passive"))
      (node (ref "C24") (pin "1") (pinfunction "1_1") (pintype "passive"))
      (node (ref "C25") (pin "1") (pinfunction "1_1") (pintype "passive"))
      (node (ref "C26") (pin "1") (pinfunction "1_1") (pintype "passive"))
      (node (ref "C27") (pin "1") (pinfunction "1_1") (pintype "passive"))
      (node (ref "C3") (pin "2") (pinfunction "2_2") (pintype "passive"))
      (node (ref "C30") (pin "2") (pinfunction "2_2") (pintype "passive"))
      (node (ref "C31") (pin "2") (pinfunction "2_2") (pintype "passive"))
      (node (ref "C34") (pin "1") (pinfunction "1_1") (pintype "passive"))
      (node (ref "C35") (pin "2") (pinfunction "2_2") (pintype "passive"))
      (node (ref "C36") (pin "1") (pinfunction "1_1") (pintype "passive"))
      (node (ref "C37") (pin "1") (pinfunction "1_1") (pintype "passive"))
      (node (ref "C38") (pin "2") (pinfunction "2_2") (pintype "passive"))
      (node (ref "C39") (pin "2") (pinfunction "2_2") (pintype "passive"))
      (node (ref "C4") (pin "1") (pinfunction "1_1") (pintype "passive"))
      (node (ref "C40") (pin "1") (pinfunction "1_1") (pintype "passive"))
      (node (ref "C41") (pin "2") (pinfunction "2_2") (pintype "passive"))
      (node (ref "C42") (pin "1") (pinfunction "1_1") (pintype "passive"))
      (node (ref "C43") (pin "2") (pinfunction "2_2") (pintype "passive"))
      (node (ref "C44") (pin "1") (pinfunction "1_1") (pintype "passive"))
      (node (ref "C45") (pin "2") (pinfunction "2_2") (pintype "passive"))
      (node (ref "C46") (pin "1") (pinfunction "1_1") (pintype "passive"))
      (node (ref "C47") (pin "1") (pinfunction "1_1") (pintype "passive"))
      (node (ref "C48") (pin "1") (pinfunction "1_1") (pintype "passive"))
      (node (ref "C49") (pin "1") (pinfunction "1_1") (pintype "passive"))
      (node (ref "C5") (pin "1") (pinfunction "1_1") (pintype "passive"))
      (node (ref "C50") (pin "2") (pinfunction "2_2") (pintype "passive"))
      (node (ref "C53") (pin "2") (pinfunction "2_2") (pintype "passive"))
      (node (ref "C55") (pin "1") (pinfunction "1_1") (pintype "passive"))
      (node (ref "C56") (pin "1") (pinfunction "1_1") (pintype "passive"))
      (node (ref "C57") (pin "1") (pinfunction "1_1") (pintype "passive"))
      (node (ref "C58") (pin "1") (pinfunction "1_1") (pintype "passive"))
      (node (ref "C59") (pin "1") (pinfunction "1_1") (pintype "passive"))
      (node (ref "C6") (pin "1") (pinfunction "1_1") (pintype "passive"))
      (node (ref "C60") (pin "1") (pinfunction "1_1") (pintype "passive"))
      (node (ref "C61") (pin "1") (pinfunction "1_1") (pintype "passive"))
      (node (ref "C62") (pin "1") (pinfunction "1_1") (pintype "passive"))
      (node (ref "C63") (pin "2") (pinfunction "2_2") (pintype "passive"))
      (node (ref "C64") (pin "1") (pinfunction "1_1") (pintype "passive"))
      (node (ref "C65") (pin "2") (pinfunction "2_2") (pintype "passive"))
      (node (ref "C66") (pin "1") (pinfunction "1_1") (pintype "passive"))
      (node (ref "C67") (pin "2") (pinfunction "2_2") (pintype "passive"))
      (node (ref "C68") (pin "1") (pinfunction "1_1") (pintype "passive"))
      (node (ref "C69") (pin "2") (pinfunction "2_2") (pintype "passive"))
      (node (ref "C7") (pin "2") (pinfunction "2_2") (pintype "passive"))
      (node (ref "C70") (pin "1") (pinfunction "1_1") (pintype "passive"))
      (node (ref "C71") (pin "1") (pinfunction "1_1") (pintype "passive"))
      (node (ref "C72") (pin "1") (pinfunction "1_1") (pintype "passive"))
      (node (ref "C73") (pin "1") (pinfunction "1_1") (pintype "passive"))
      (node (ref "C74") (pin "1") (pinfunction "1_1") (pintype "passive"))
      (node (ref "C8") (pin "1") (pinfunction "1_1") (pintype "passive"))
      (node (ref "C9") (pin "1") (pinfunction "1_1") (pintype "passive"))
      (node (ref "IC1") (pin "1") (pinfunction "C1_1") (pintype "passive"))
      (node (ref "IC1") (pin "3") (pinfunction "double_cathode_3") (pintype "passive"))
      (node (ref "IC10") (pin "8") (pinfunction "V+_8") (pintype "passive"))
      (node (ref "IC13") (pin "5") (pinfunction "GND_5") (pintype "passive"))
      (node (ref "IC13") (pin "7") (pinfunction "~EN_7") (pintype "passive"))
      (node (ref "IC14") (pin "1") (pinfunction "CHAIN_1") (pintype "passive"))
      (node (ref "IC14") (pin "10") (pintype "passive"))
      (node (ref "IC14") (pin "12") (pinfunction "RDL/SDI_12") (pintype "passive"))
      (node (ref "IC14") (pin "16") (pintype "passive"))
      (node (ref "IC14") (pin "3") (pintype "passive"))
      (node (ref "IC14") (pin "6") (pintype "passive"))
      (node (ref "IC17") (pin "3") (pinfunction "+IN_A_3") (pintype "passive"))
      (node (ref "IC2") (pin "3") (pinfunction "double_cathode_3") (pintype "passive"))
      (node (ref "IC3") (pin "3") (pinfunction "double_cathode_3") (pintype "passive"))
      (node (ref "IC4") (pin "12") (pinfunction "GND_12") (pintype "passive"))
      (node (ref "IC4") (pin "28") (pinfunction "+_28") (pintype "passive"))
      (node (ref "IC5") (pin "12") (pinfunction "GND_12") (pintype "passive"))
      (node (ref "IC5") (pin "23") (pintype "passive"))
      (node (ref "IC5") (pin "25") (pintype "passive"))
      (node (ref "IC5") (pin "26") (pintype "passive"))
      (node (ref "IC5") (pin "6") (pintype "passive"))
      (node (ref "IC5") (pin "7") (pintype "passive"))
      (node (ref "IC6") (pin "3") (pintype "passive"))
      (node (ref "IC6") (pin "4") (pintype "passive"))
      (node (ref "IC6") (pin "5") (pintype "passive"))
      (node (ref "IC6") (pin "8") (pintype "passive"))
      (node (ref "IC9") (pin "1") (pintype "passive"))
      (node (ref "IC9") (pin "2") (pintype "passive"))
      (node (ref "J1") (pin "4") (pinfunction "U4_4") (pintype "bidirectional"))
      (node (ref "J1") (pin "5") (pinfunction "U5_5") (pintype "bidirectional"))
      (node (ref "J4") (pin "1") (pinfunction "I/O_1") (pintype "bidirectional"))
      (node (ref "J4") (pin "12") (pinfunction "I/O_12") (pintype "bidirectional"))
      (node (ref "J4") (pin "13") (pinfunction "I/O_13") (pintype "bidirectional"))
      (node (ref "J4") (pin "16") (pinfunction "I/O_16") (pintype "bidirectional"))
      (node (ref "J4") (pin "17") (pinfunction "I/O_17") (pintype "bidirectional"))
      (node (ref "J4") (pin "20") (pinfunction "I/O_20") (pintype "bidirectional"))
      (node (ref "J4") (pin "21") (pinfunction "I/O_21") (pintype "bidirectional"))
      (node (ref "J4") (pin "24") (pinfunction "I/O_24") (pintype "bidirectional"))
      (node (ref "J4") (pin "25") (pinfunction "I/O_25") (pintype "bidirectional"))
      (node (ref "J4") (pin "28") (pinfunction "I/O_28") (pintype "bidirectional"))
      (node (ref "J4") (pin "29") (pinfunction "I/O_29") (pintype "bidirectional"))
      (node (ref "J4") (pin "32") (pinfunction "I/O_32") (pintype "bidirectional"))
      (node (ref "J4") (pin "33") (pinfunction "I/O_33") (pintype "bidirectional"))
      (node (ref "J4") (pin "36") (pinfunction "I/O_36") (pintype "bidirectional"))
      (node (ref "J4") (pin "37") (pinfunction "I/O_37") (pintype "bidirectional"))
      (node (ref "J4") (pin "4") (pinfunction "I/O_4") (pintype "bidirectional"))
      (node (ref "J4") (pin "40") (pinfunction "I/O_40") (pintype "bidirectional"))
      (node (ref "J4") (pin "41") (pinfunction "I/O_41") (pintype "bidirectional"))
      (node (ref "J4") (pin "44") (pinfunction "I/O_44") (pintype "bidirectional"))
      (node (ref "J4") (pin "45") (pinfunction "I/O_45") (pintype "bidirectional"))
      (node (ref "J4") (pin "48") (pinfunction "I/O_48") (pintype "bidirectional"))
      (node (ref "J4") (pin "49") (pinfunction "I/O_49") (pintype "bidirectional"))
      (node (ref "J4") (pin "5") (pinfunction "I/O_5") (pintype "bidirectional"))
      (node (ref "J4") (pin "52") (pinfunction "I/O_52") (pintype "bidirectional"))
      (node (ref "J4") (pin "53") (pinfunction "I/O_53") (pintype "bidirectional"))
      (node (ref "J4") (pin "56") (pinfunction "I/O_56") (pintype "bidirectional"))
      (node (ref "J4") (pin "57") (pinfunction "I/O_57") (pintype "bidirectional"))
      (node (ref "J4") (pin "60") (pinfunction "I/O_60") (pintype "bidirectional"))
      (node (ref "J4") (pin "61") (pinfunction "I/O_61") (pintype "bidirectional"))
      (node (ref "J4") (pin "64") (pinfunction "I/O_64") (pintype "bidirectional"))
      (node (ref "J4") (pin "8") (pinfunction "I/O_8") (pintype "bidirectional"))
      (node (ref "J4") (pin "9") (pinfunction "I/O_9") (pintype "bidirectional"))
      (node (ref "R1") (pin "1") (pinfunction "1_1") (pintype "passive"))
      (node (ref "R18") (pin "1") (pinfunction "1_1") (pintype "passive"))
      (node (ref "R2") (pin "1") (pinfunction "1_1") (pintype "passive"))
    )
    (net (code "33") (name "Net-(C51-Pad1)") (class "Default")
      (node (ref "C51") (pin "1") (pinfunction "1_1") (pintype "passive"))
      (node (ref "R22") (pin "2") (pinfunction "2_2") (pintype "passive"))
      (node (ref "R23") (pin "1") (pinfunction "1_1") (pintype "passive"))
    )
    (net (code "34") (name "Net-(C55-Pad2)") (class "Default")
      (node (ref "C55") (pin "2") (pinfunction "2_2") (pintype "passive"))
      (node (ref "R21") (pin "2") (pinfunction "2_2") (pintype "passive"))
      (node (ref "R22") (pin "1") (pinfunction "1_1") (pintype "passive"))
    )
    (net (code "35") (name "Net-(IC4--)") (class "Default")
      (node (ref "IC4") (pin "2") (pinfunction "-_2") (pintype "passive"))
      (node (ref "T1") (pin "1") (pinfunction "D_1") (pintype "passive"))
    )
    (net (code "36") (name "Net-(IC4-A0)") (class "Default")
      (node (ref "IC4") (pin "17") (pinfunction "A0_17") (pintype "passive"))
      (node (ref "R14") (pin "2") (pinfunction "2_2") (pintype "passive"))
    )
    (net (code "37") (name "Net-(IC4-A1)") (class "Default")
      (node (ref "IC4") (pin "16") (pinfunction "A1_16") (pintype "passive"))
      (node (ref "R13") (pin "2") (pinfunction "2_2") (pintype "passive"))
    )
    (net (code "38") (name "Net-(IC4-A2)") (class "Default")
      (node (ref "IC4") (pin "15") (pinfunction "A2_15") (pintype "passive"))
      (node (ref "R12") (pin "2") (pinfunction "2_2") (pintype "passive"))
    )
    (net (code "39") (name "Net-(IC4-Pad4)") (class "Default")
      (node (ref "IC4") (pin "4") (pintype "passive"))
      (node (ref "IC4") (pin "5") (pintype "passive"))
      (node (ref "IC4") (pin "6") (pintype "passive"))
      (node (ref "IC4") (pin "7") (pintype "passive"))
      (node (ref "R4") (pin "1") (pinfunction "1_1") (pintype "passive"))
    )
    (net (code "40") (name "Net-(IC4-Pad23)") (class "Default")
      (node (ref "IC4") (pin "23") (pintype "passive"))
      (node (ref "IC4") (pin "24") (pintype "passive"))
      (node (ref "IC4") (pin "25") (pintype "passive"))
      (node (ref "IC4") (pin "26") (pintype "passive"))
      (node (ref "R4") (pin "2") (pinfunction "2_2") (pintype "passive"))
    )
    (net (code "41") (name "Net-(IC5--)") (class "Default")
      (node (ref "IC5") (pin "2") (pinfunction "-_2") (pintype "passive"))
      (node (ref "IC8") (pin "1") (pinfunction "-IN_1") (pintype "input"))
      (node (ref "IC8") (pin "4") (pinfunction "+IN_4") (pintype "input"))
    )
    (net (code "42") (name "Net-(IC5-A0)") (class "Default")
      (node (ref "IC5") (pin "17") (pinfunction "A0_17") (pintype "passive"))
      (node (ref "R15") (pin "2") (pinfunction "2_2") (pintype "passive"))
    )
    (net (code "43") (name "Net-(IC5-A1)") (class "Default")
      (node (ref "IC5") (pin "16") (pinfunction "A1_16") (pintype "passive"))
      (node (ref "R16") (pin "2") (pinfunction "2_2") (pintype "passive"))
    )
    (net (code "44") (name "Net-(IC5-A2)") (class "Default")
      (node (ref "IC5") (pin "15") (pinfunction "A2_15") (pintype "passive"))
      (node (ref "R17") (pin "2") (pinfunction "2_2") (pintype "passive"))
    )
    (net (code "45") (name "Net-(IC7-OUT)") (class "Default")
      (node (ref "C21") (pin "2") (pinfunction "2_2") (pintype "passive"))
      (node (ref "IC7") (pin "6") (pinfunction "OUT_6") (pintype "passive"))
      (node (ref "R3") (pin "1") (pinfunction "1_1") (pintype "passive"))
    )
    (net (code "46") (name "Net-(IC8-RG-Pad2)") (class "Default")
      (node (ref "IC8") (pin "2") (pinfunction "RG_2") (pintype "passive"))
      (node (ref "R5") (pin "2") (pinfunction "2_2") (pintype "passive"))
      (node (ref "R6") (pin "2") (pinfunction "2_2") (pintype "passive"))
    )
    (net (code "47") (name "Net-(IC8-RG-Pad3)") (class "Default")
      (node (ref "IC8") (pin "3") (pinfunction "RG_3") (pintype "passive"))
      (node (ref "R7") (pin "2") (pinfunction "2_2") (pintype "passive"))
    )
    (net (code "48") (name "Net-(IC10A--IN_A)") (class "Default")
      (node (ref "C28") (pin "1") (pinfunction "1_1") (pintype "passive"))
      (node (ref "IC10") (pin "2") (pinfunction "-IN_A_2") (pintype "passive"))
      (node (ref "R11") (pin "2") (pinfunction "2_2") (pintype "passive"))
      (node (ref "T1") (pin "3") (pinfunction "S_3") (pintype "passive"))
    )
    (net (code "49") (name "Net-(IC10A-OUT_A)") (class "Default")
      (node (ref "C28") (pin "2") (pinfunction "2_2") (pintype "passive"))
      (node (ref "IC10") (pin "1") (pinfunction "OUT_A_1") (pintype "passive"))
      (node (ref "R8") (pin "1") (pinfunction "1_1") (pintype "passive"))
    )
    (net (code "50") (name "Net-(IC10B--IN_B)") (class "Default")
      (node (ref "C52") (pin "1") (pinfunction "1_1") (pintype "passive"))
      (node (ref "IC10") (pin "6") (pinfunction "-IN_B_6") (pintype "passive"))
      (node (ref "R26") (pin "2") (pinfunction "2_2") (pintype "passive"))
      (node (ref "T2") (pin "3") (pinfunction "S_3") (pintype "passive"))
    )
    (net (code "51") (name "Net-(IC10B-OUT_B)") (class "Default")
      (node (ref "C52") (pin "2") (pinfunction "2_2") (pintype "passive"))
      (node (ref "IC10") (pin "7") (pinfunction "OUT_B_7") (pintype "passive"))
      (node (ref "R19") (pin "1") (pinfunction "1_1") (pintype "passive"))
    )
    (net (code "52") (name "Net-(IC11-+IN)") (class "Default")
      (node (ref "IC11") (pin "1") (pinfunction "-IN_1") (pintype "input"))
      (node (ref "IC11") (pin "4") (pinfunction "+IN_4") (pintype "input"))
      (node (ref "IC5") (pin "28") (pinfunction "+_28") (pintype "passive"))
    )
    (net (code "53") (name "Net-(IC11-RG-Pad2)") (class "Default")
      (node (ref "IC11") (pin "2") (pinfunction "RG_2") (pintype "passive"))
      (node (ref "R5") (pin "1") (pinfunction "1_1") (pintype "passive"))
      (node (ref "R6") (pin "1") (pinfunction "1_1") (pintype "passive"))
    )
    (net (code "54") (name "Net-(IC11-RG-Pad3)") (class "Default")
      (node (ref "IC11") (pin "3") (pinfunction "RG_3") (pintype "passive"))
      (node (ref "R7") (pin "1") (pinfunction "1_1") (pintype "passive"))
    )
    (net (code "55") (name "Net-(IC12-IN+)") (class "Default")
      (node (ref "IC12") (pin "3") (pinfunction "IN+_3") (pintype "passive"))
      (node (ref "R18") (pin "2") (pinfunction "2_2") (pintype "passive"))
      (node (ref "R9") (pin "1") (pinfunction "1_1") (pintype "passive"))
    )
    (net (code "56") (name "Net-(IC12-OUT)") (class "Default")
      (node (ref "C29") (pin "1") (pinfunction "1_1") (pintype "passive"))
      (node (ref "IC12") (pin "6") (pinfunction "OUT_6") (pintype "passive"))
      (node (ref "R10") (pin "1") (pinfunction "1_1") (pintype "passive"))
    )
    (net (code "57") (name "Net-(IC13-COM)") (class "Default")
      (node (ref "IC13") (pin "8") (pinfunction "COM_8") (pintype "passive"))
      (node (ref "R21") (pin "1") (pinfunction "1_1") (pintype "passive"))
    )
    (net (code "58") (name "Net-(IC13-IN)") (class "Default")
      (node (ref "IC13") (pin "3") (pinfunction "IN_3") (pintype "passive"))
      (node (ref "R28") (pin "2") (pinfunction "2_2") (pintype "passive"))
    )
    (net (code "59") (name "Net-(IC13-NC)") (class "Default")
      (node (ref "IC13") (pin "1") (pinfunction "NC_1") (pintype "passive"))
      (node (ref "J2") (pin "3") (pinfunction "3_3") (pintype "passive"))
    )
    (net (code "60") (name "Net-(IC14-BUSY)") (class "Default")
      (node (ref "IC14") (pin "11") (pinfunction "BUSY_11") (pintype "passive"))
      (node (ref "R27") (pin "1") (pinfunction "1_1") (pintype "passive"))
    )
    (net (code "61") (name "Net-(IC14-CNV)") (class "Default")
      (node (ref "IC14") (pin "9") (pinfunction "CNV_9") (pintype "passive"))
      (node (ref "R30") (pin "1") (pinfunction "1_1") (pintype "passive"))
    )
    (net (code "62") (name "Net-(IC14-IN+)") (class "Default")
      (node (ref "C53") (pin "1") (pinfunction "1_1") (pintype "passive"))
      (node (ref "C54") (pin "2") (pinfunction "2_2") (pintype "passive"))
      (node (ref "IC14") (pin "4") (pinfunction "IN+_4") (pintype "passive"))
      (node (ref "R20") (pin "2") (pinfunction "2_2") (pintype "passive"))
    )
    (net (code "63") (name "Net-(IC14-IN-)") (class "Default")
      (node (ref "C54") (pin "1") (pinfunction "1_1") (pintype "passive"))
      (node (ref "C57") (pin "2") (pinfunction "2_2") (pintype "passive"))
      (node (ref "IC14") (pin "5") (pinfunction "IN-_5") (pintype "passive"))
      (node (ref "R29") (pin "2") (pinfunction "2_2") (pintype "passive"))
    )
    (net (code "64") (name "Net-(IC14-SCK)") (class "Default")
      (node (ref "IC14") (pin "13") (pinfunction "SCK_13") (pintype "passive"))
      (node (ref "R25") (pin "1") (pinfunction "1_1") (pintype "passive"))
    )
    (net (code "65") (name "Net-(IC14-SDO)") (class "Default")
      (node (ref "IC14") (pin "14") (pinfunction "SDO_14") (pintype "passive"))
      (node (ref "R24") (pin "1") (pinfunction "1_1") (pintype "passive"))
    )
    (net (code "66") (name "Net-(IC15-+IN1)") (class "Default")
      (node (ref "IC15") (pin "8") (pinfunction "+IN1_8") (pintype "passive"))
      (node (ref "J3") (pin "2") (pinfunction "2_2") (pintype "passive"))
    )
    (net (code "67") (name "Net-(IC15--IN1)") (class "Default")
      (node (ref "IC15") (pin "1") (pinfunction "-IN1_1") (pintype "passive"))
      (node (ref "IC15") (pin "4") (pinfunction "OUT1_4") (pintype "passive"))
      (node (ref "R20") (pin "1") (pinfunction "1_1") (pintype "passive"))
    )
    (net (code "68") (name "Net-(IC15-OUT2)") (class "Default")
      (node (ref "IC15") (pin "5") (pinfunction "OUT2_5") (pintype "passive"))
      (node (ref "R29") (pin "1") (pinfunction "1_1") (pintype "passive"))
    )
    (net (code "69") (name "Net-(IC16-IN+)") (class "Default")
      (node (ref "C56") (pin "2") (pinfunction "2_2") (pintype "passive"))
      (node (ref "IC16") (pin "3") (pinfunction "IN+_3") (pintype "passive"))
      (node (ref "R23") (pin "2") (pinfunction "2_2") (pintype "passive"))
    )
    (net (code "70") (name "Net-(IC16-IN-)") (class "Default")
      (node (ref "C51") (pin "2") (pinfunction "2_2") (pintype "passive"))
      (node (ref "IC16") (pin "2") (pinfunction "IN-_2") (pintype "passive"))
      (node (ref "IC16") (pin "6") (pinfunction "OUT_6") (pintype "passive"))
      (node (ref "J3") (pin "3") (pinfunction "3_3") (pintype "passive"))
    )
    (net (code "71") (name "Net-(IC17A--IN_A)") (class "Default")
      (node (ref "IC17") (pin "2") (pinfunction "-IN_A_2") (pintype "passive"))
      (node (ref "R31") (pin "2") (pinfunction "2_2") (pintype "passive"))
      (node (ref "R32") (pin "1") (pinfunction "1_1") (pintype "passive"))
    )
    (net (code "72") (name "Net-(IC17B--IN_B)") (class "Default")
      (node (ref "IC17") (pin "6") (pinfunction "-IN_B_6") (pintype "passive"))
      (node (ref "IC17") (pin "7") (pinfunction "OUT_B_7") (pintype "passive"))
      (node (ref "R31") (pin "1") (pinfunction "1_1") (pintype "passive"))
    )
    (net (code "73") (name "Net-(J1-Pad10)") (class "Default")
      (node (ref "J1") (pin "10") (pinfunction "10_10") (pintype "passive"))
      (node (ref "R1") (pin "2") (pinfunction "2_2") (pintype "passive"))
    )
    (net (code "74") (name "Net-(J1-Pad11)") (class "Default")
      (node (ref "J1") (pin "11") (pinfunction "11_11") (pintype "passive"))
      (node (ref "R2") (pin "2") (pinfunction "2_2") (pintype "passive"))
    )
    (net (code "75") (name "Net-(T1-G)") (class "Default")
      (node (ref "R8") (pin "2") (pinfunction "2_2") (pintype "passive"))
      (node (ref "T1") (pin "2") (pinfunction "G_2") (pintype "passive"))
    )
    (net (code "76") (name "Net-(T2-G)") (class "Default")
      (node (ref "R19") (pin "2") (pinfunction "2_2") (pintype "passive"))
      (node (ref "T2") (pin "2") (pinfunction "G_2") (pintype "passive"))
    )
    (net (code "77") (name "unconnected-(IC7-~PD-Pad8)") (class "Default")
      (node (ref "IC7") (pin "8") (pinfunction "~PD_8") (pintype "passive"))
    )
    (net (code "78") (name "unconnected-(IC12-~PD-Pad8)") (class "Default")
      (node (ref "IC12") (pin "8") (pinfunction "~PD_8") (pintype "passive"))
    )
    (net (code "79") (name "unconnected-(IC16-~PD-Pad8)") (class "Default")
      (node (ref "IC16") (pin "8") (pinfunction "~PD_8") (pintype "passive"))
    )
    (net (code "80") (name "unconnected-(J1A-U3-Pad3)") (class "Default")
      (node (ref "J1") (pin "3") (pinfunction "U3_3") (pintype "bidirectional"))
    )
    (net (code "81") (name "unconnected-(J1A-U8-Pad8)") (class "Default")
      (node (ref "J1") (pin "8") (pinfunction "U8_8") (pintype "bidirectional"))
    )
    (net (code "82") (name "unconnected-(J4-I{slash}O-Pad3)") (class "Default")
      (node (ref "J4") (pin "3") (pinfunction "I/O_3") (pintype "bidirectional+no_connect"))
    )
    (net (code "83") (name "unconnected-(J4-I{slash}O-Pad7)") (class "Default")
      (node (ref "J4") (pin "7") (pinfunction "I/O_7") (pintype "bidirectional+no_connect"))
    )
    (net (code "84") (name "unconnected-(J4-I{slash}O-Pad11)") (class "Default")
      (node (ref "J4") (pin "11") (pinfunction "I/O_11") (pintype "bidirectional+no_connect"))
    )
    (net (code "85") (name "unconnected-(J4-I{slash}O-Pad15)") (class "Default")
      (node (ref "J4") (pin "15") (pinfunction "I/O_15") (pintype "bidirectional+no_connect"))
    )
    (net (code "86") (name "unconnected-(J4-I{slash}O-Pad19)") (class "Default")
      (node (ref "J4") (pin "19") (pinfunction "I/O_19") (pintype "bidirectional+no_connect"))
    )
    (net (code "87") (name "unconnected-(J4-I{slash}O-Pad23)") (class "Default")
      (node (ref "J4") (pin "23") (pinfunction "I/O_23") (pintype "bidirectional+no_connect"))
    )
    (net (code "88") (name "unconnected-(J4-I{slash}O-Pad27)") (class "Default")
      (node (ref "J4") (pin "27") (pinfunction "I/O_27") (pintype "bidirectional+no_connect"))
    )
    (net (code "89") (name "unconnected-(J4-I{slash}O-Pad31)") (class "Default")
      (node (ref "J4") (pin "31") (pinfunction "I/O_31") (pintype "bidirectional+no_connect"))
    )
    (net (code "90") (name "unconnected-(J4-I{slash}O-Pad34)") (class "Default")
      (node (ref "J4") (pin "34") (pinfunction "I/O_34") (pintype "bidirectional+no_connect"))
    )
    (net (code "91") (name "unconnected-(J4-I{slash}O-Pad38)") (class "Default")
      (node (ref "J4") (pin "38") (pinfunction "I/O_38") (pintype "bidirectional+no_connect"))
    )
    (net (code "92") (name "unconnected-(J4-I{slash}O-Pad42)") (class "Default")
      (node (ref "J4") (pin "42") (pinfunction "I/O_42") (pintype "bidirectional+no_connect"))
    )
    (net (code "93") (name "unconnected-(J4-I{slash}O-Pad43)") (class "Default")
      (node (ref "J4") (pin "43") (pinfunction "I/O_43") (pintype "bidirectional+no_connect"))
    )
    (net (code "94") (name "unconnected-(J4-I{slash}O-Pad46)") (class "Default")
      (node (ref "J4") (pin "46") (pinfunction "I/O_46") (pintype "bidirectional+no_connect"))
    )
    (net (code "95") (name "unconnected-(J4-I{slash}O-Pad50)") (class "Default")
      (node (ref "J4") (pin "50") (pinfunction "I/O_50") (pintype "bidirectional+no_connect"))
    )
    (net (code "96") (name "unconnected-(J4-I{slash}O-Pad54)") (class "Default")
      (node (ref "J4") (pin "54") (pinfunction "I/O_54") (pintype "bidirectional+no_connect"))
    )
    (net (code "97") (name "unconnected-(J4-I{slash}O-Pad55)") (class "Default")
      (node (ref "J4") (pin "55") (pinfunction "I/O_55") (pintype "bidirectional+no_connect"))
    )
    (net (code "98") (name "unconnected-(J4-I{slash}O-Pad58)") (class "Default")
      (node (ref "J4") (pin "58") (pinfunction "I/O_58") (pintype "bidirectional+no_connect"))
    )
    (net (code "99") (name "unconnected-(J4-I{slash}O-Pad62)") (class "Default")
      (node (ref "J4") (pin "62") (pinfunction "I/O_62") (pintype "bidirectional+no_connect"))
    )
  )
)
